# SPI_SD.net
KiCad netlist of a schematic drawn in Altium Designer
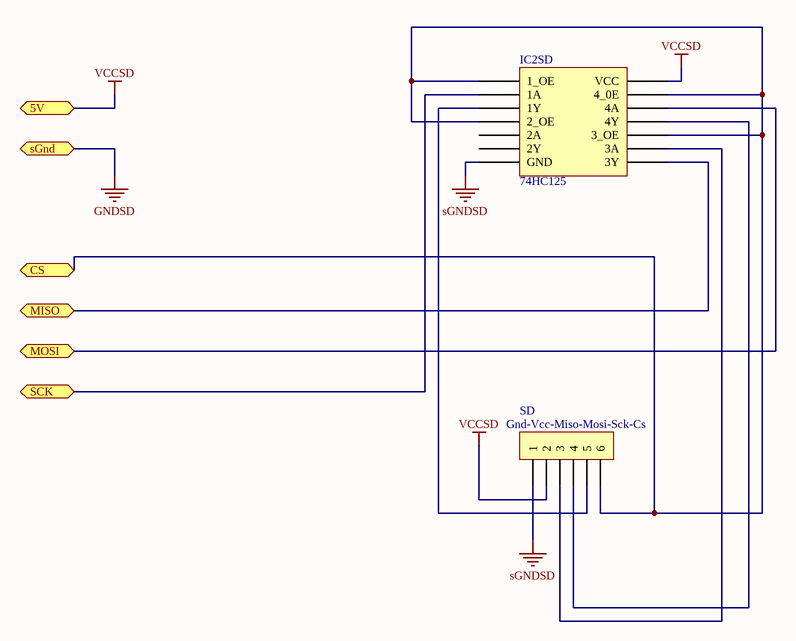
[diagram p0: SPI_SD.SchDoc]

(export (version "E")
  (design (tool "Eeschema 10.0.6"))
  (components
    (comp (ref "IC2SD") (value "74HC125") (footprint "DIP14B") (libsource (lib "IDTILab") (part "74HC125")))
    (comp (ref "SD")
      (value "Gnd-Vcc-Miso-Mosi-Sck-Cs")
      (footprint "CON6")
      (description "Conector 6")
      (libsource (lib "DIE-SA Ingenieria") (part "CON6"))
    )
  )
  (nets
    (net (code "1") (name "/CS") (class "Default")
      (node (ref "IC2SD") (pin "1") (pinfunction "1_OE_1") (pintype "passive"))
      (node (ref "IC2SD") (pin "10") (pinfunction "3_OE_10") (pintype "passive"))
      (node (ref "IC2SD") (pin "13") (pinfunction "4_0E_13") (pintype "passive"))
      (node (ref "IC2SD") (pin "4") (pinfunction "2_OE_4") (pintype "passive"))
      (node (ref "SD") (pin "6") (pinfunction "6_6") (pintype "passive"))
    )
    (net (code "2") (name "/MISO") (class "Default")
      (node (ref "IC2SD") (pin "8") (pinfunction "3Y_8") (pintype "passive"))
    )
    (net (code "3") (name "/MOSI") (class "Default")
      (node (ref "IC2SD") (pin "12") (pinfunction "4A_12") (pintype "passive"))
    )
    (net (code "4") (name "/SCK") (class "Default")
      (node (ref "IC2SD") (pin "2") (pinfunction "1A_2") (pintype "passive"))
    )
    (net (code "6") (name "Net-(IC2SD-1Y)") (class "Default")
      (node (ref "IC2SD") (pin "3") (pinfunction "1Y_3") (pintype "passive"))
      (node (ref "SD") (pin "5") (pinfunction "5_5") (pintype "passive"))
    )
    (net (code "7") (name "Net-(IC2SD-3A)") (class "Default")
      (node (ref "IC2SD") (pin "9") (pinfunction "3A_9") (pintype "passive"))
      (node (ref "SD") (pin "3") (pinfunction "3_3") (pintype "passive"))
    )
    (net (code "8") (name "Net-(IC2SD-4Y)") (class "Default")
      (node (ref "IC2SD") (pin "11") (pinfunction "4Y_11") (pintype "passive"))
      (node (ref "SD") (pin "4") (pinfunction "4_4") (pintype "passive"))
    )
    (net (code "9") (name "VCCSD") (class "Default")
      (node (ref "IC2SD") (pin "14") (pinfunction "VCC_14") (pintype "passive"))
      (node (ref "SD") (pin "2") (pinfunction "2_2") (pintype "passive"))
    )
    (net (code "10") (name "sGNDSD") (class "Default")
      (node (ref "IC2SD") (pin "7") (pinfunction "GND_7") (pintype "passive"))
      (node (ref "SD") (pin "1") (pinfunction "1_1") (pintype "passive"))
    )
    (net (code "11") (name "unconnected-(IC2SD-2A-Pad5)") (class "Default")
      (node (ref "IC2SD") (pin "5") (pinfunction "2A_5") (pintype "passive"))
    )
    (net (code "12") (name "unconnected-(IC2SD-2Y-Pad6)") (class "Default")
      (node (ref "IC2SD") (pin "6") (pinfunction "2Y_6") (pintype "passive"))
    )
  )
)
